# Qwiic_Shield_for_Arduino.net
KiCad netlist of a schematic drawn in EAGLE
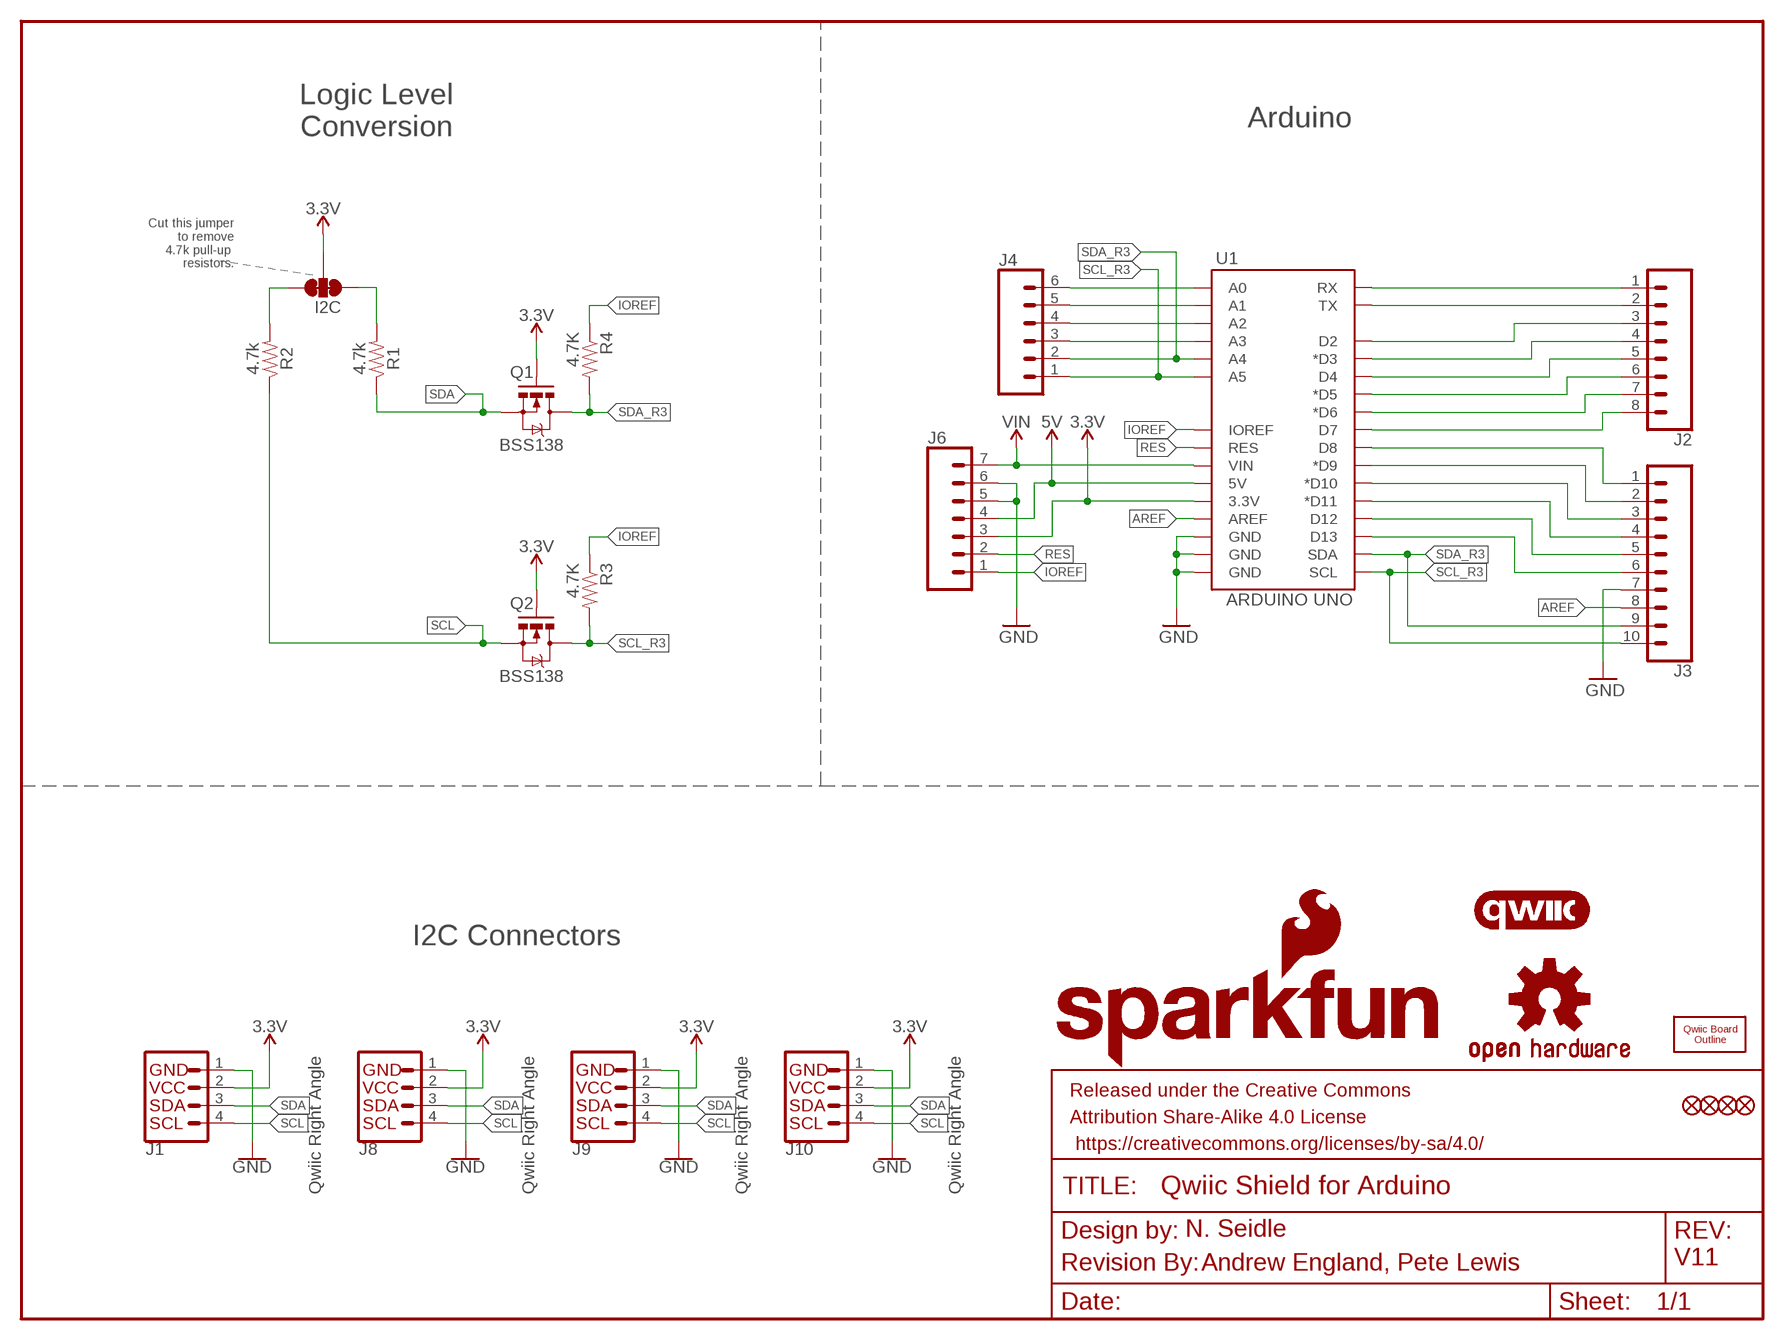
[diagram p0: schematic, sheet 1]

(export (version "E")
  (design (tool "Eeschema 10.0.6"))
  (components
    (comp (ref "FD1")
      (value "FIDUCIAL1X2")
      (footprint "eagle-import:FIDUCIAL-1X2")
      (libsource (lib "eagle-import") (part "FIDUCIAL1X2"))
    )
    (comp (ref "FD2")
      (value "FIDUCIAL1X2")
      (footprint "eagle-import:FIDUCIAL-1X2")
      (libsource (lib "eagle-import") (part "FIDUCIAL1X2"))
    )
    (comp (ref "FD3")
      (value "FIDUCIAL1X2")
      (footprint "eagle-import:FIDUCIAL-1X2")
      (libsource (lib "eagle-import") (part "FIDUCIAL1X2"))
    )
    (comp (ref "FD4")
      (value "FIDUCIAL1X2")
      (footprint "eagle-import:FIDUCIAL-1X2")
      (libsource (lib "eagle-import") (part "FIDUCIAL1X2"))
    )
    (comp (ref "FRAME1")
      (value "FRAME-LETTER")
      (footprint "eagle-import:CREATIVE_COMMONS")
      (libsource (lib "eagle-import") (part "FRAME-LETTER"))
    )
    (comp (ref "I2C")
      (value "JUMPER-SMT_3_2-NC_TRACE_SILK")
      (footprint "eagle-import:SMT-JUMPER_3_2-NC_TRACE_SILK")
      (libsource (lib "eagle-import") (part "JUMPER-SMT_3_2-NC_TRACE_SILK"))
    )
    (comp (ref "J1")
      (value "Qwiic Right Angle")
      (footprint "eagle-import:1X04_1MM_RA")
      (libsource (lib "eagle-import") (part "I2C_STANDARDQWIIC"))
    )
    (comp (ref "J2")
      (value "CONN_08NO_SILK_FEMALE_PTH")
      (footprint "eagle-import:1X08_NO_SILK")
      (libsource (lib "eagle-import") (part "CONN_08NO_SILK_FEMALE_PTH"))
    )
    (comp (ref "J3")
      (value "CONN_10NO_SILK_PTH_FEMALE")
      (footprint "eagle-import:1X10_NO_SILK")
      (libsource (lib "eagle-import") (part "CONN_10NO_SILK_PTH_FEMALE"))
    )
    (comp (ref "J4")
      (value "CONN_06NO_SILK_FEMALE_PTH")
      (footprint "eagle-import:1X06_NO_SILK")
      (libsource (lib "eagle-import") (part "CONN_06NO_SILK_FEMALE_PTH"))
    )
    (comp (ref "J6")
      (value "CONN_07NO_SILK")
      (footprint "eagle-import:1X07_NO_SILK")
      (libsource (lib "eagle-import") (part "CONN_07NO_SILK"))
    )
    (comp (ref "J8")
      (value "Qwiic Right Angle")
      (footprint "eagle-import:1X04_1MM_RA")
      (libsource (lib "eagle-import") (part "I2C_STANDARDQWIIC"))
    )
    (comp (ref "J9")
      (value "Qwiic Right Angle")
      (footprint "eagle-import:1X04_1MM_RA")
      (libsource (lib "eagle-import") (part "I2C_STANDARDQWIIC"))
    )
    (comp (ref "J10")
      (value "Qwiic Right Angle")
      (footprint "eagle-import:1X04_1MM_RA")
      (libsource (lib "eagle-import") (part "I2C_STANDARDQWIIC"))
    )
    (comp (ref "LOGO1")
      (value "OSHW-LOGOMINI")
      (footprint "eagle-import:OSHW-LOGO-MINI")
      (libsource (lib "eagle-import") (part "OSHW-LOGOMINI"))
    )
    (comp (ref "LOGO2")
      (value "REVISION")
      (footprint "eagle-import:REVISION")
      (libsource (lib "eagle-import") (part "REVISION"))
    )
    (comp (ref "LOGO3")
      (value "QWIIC_LOGO_6MM")
      (footprint "eagle-import:QWIIC_6MM")
      (libsource (lib "eagle-import") (part "QWIIC_LOGO_6MM"))
    )
    (comp (ref "Q1")
      (value "BSS138")
      (footprint "eagle-import:SOT23-3")
      (libsource (lib "eagle-import") (part "MOSFET-NCHANNELBSS138"))
    )
    (comp (ref "Q2")
      (value "BSS138")
      (footprint "eagle-import:SOT23-3")
      (libsource (lib "eagle-import") (part "MOSFET-NCHANNELBSS138"))
    )
    (comp (ref "R1")
      (value "4.7k")
      (footprint "eagle-import:0603")
      (libsource (lib "eagle-import") (part "4.7KOHM-0603-1/10W-1%"))
    )
    (comp (ref "R2")
      (value "4.7k")
      (footprint "eagle-import:0603")
      (libsource (lib "eagle-import") (part "4.7KOHM-0603-1/10W-1%"))
    )
    (comp (ref "R3")
      (value "4.7K")
      (footprint "eagle-import:0603-RES")
      (libsource (lib "eagle-import") (part "4.7KOHM-1/10W-1%(0603)"))
    )
    (comp (ref "R4")
      (value "4.7K")
      (footprint "eagle-import:0603-RES")
      (libsource (lib "eagle-import") (part "4.7KOHM-1/10W-1%(0603)"))
    )
    (comp (ref "U$2")
      (value "SFE_LOGO_NAME_FLAME.1_INCH")
      (footprint "eagle-import:SFE_LOGO_NAME_FLAME_.1")
      (libsource (lib "eagle-import") (part "SFE_LOGO_NAME_FLAME.1_INCH"))
    )
    (comp (ref "U$3")
      (value "QWIIC_BOARD_OUTLINEH")
      (footprint "eagle-import:QWIIC_BOARD_MOUNT_HOLES")
      (libsource (lib "eagle-import") (part "QWIIC_BOARD_OUTLINEH"))
    )
    (comp (ref "U1")
      (value "ARDUINO UNO")
      (footprint "eagle-import:UNO_R3_SHIELD_NOLABELS")
      (libsource (lib "eagle-import") (part "ARDUINO_R3_SHIELDNOLABELS"))
    )
  )
  (nets
    (net (code "1") (name "3.3V") (class "Default")
      (node (ref "I2C") (pin "2") (pinfunction "2_2") (pintype "passive"))
      (node (ref "J1") (pin "2") (pinfunction "2_2") (pintype "power_in"))
      (node (ref "J10") (pin "2") (pinfunction "2_2") (pintype "power_in"))
      (node (ref "J6") (pin "3") (pinfunction "3_3") (pintype "passive"))
      (node (ref "J8") (pin "2") (pinfunction "2_2") (pintype "power_in"))
      (node (ref "J9") (pin "2") (pinfunction "2_2") (pintype "power_in"))
      (node (ref "Q1") (pin "1") (pinfunction "G_1") (pintype "passive"))
      (node (ref "Q2") (pin "1") (pinfunction "G_1") (pintype "passive"))
      (node (ref "U1") (pin "3.3V") (pinfunction "3.3V_3.3V") (pintype "bidirectional"))
    )
    (net (code "2") (name "5V") (class "Default")
      (node (ref "J6") (pin "4") (pinfunction "4_4") (pintype "passive"))
      (node (ref "U1") (pin "5V") (pinfunction "5V_5V") (pintype "bidirectional"))
    )
    (net (code "3") (name "AREF") (class "Default")
      (node (ref "J3") (pin "8") (pinfunction "8_8") (pintype "passive"))
      (node (ref "U1") (pin "AREF") (pinfunction "AREF_AREF") (pintype "bidirectional"))
    )
    (net (code "4") (name "GND") (class "Default")
      (node (ref "J1") (pin "1") (pinfunction "1_1") (pintype "power_in"))
      (node (ref "J10") (pin "1") (pinfunction "1_1") (pintype "power_in"))
      (node (ref "J3") (pin "7") (pinfunction "7_7") (pintype "passive"))
      (node (ref "J6") (pin "5") (pinfunction "5_5") (pintype "passive"))
      (node (ref "J6") (pin "6") (pinfunction "6_6") (pintype "passive"))
      (node (ref "J8") (pin "1") (pinfunction "1_1") (pintype "power_in"))
      (node (ref "J9") (pin "1") (pinfunction "1_1") (pintype "power_in"))
      (node (ref "U1") (pin "GND@0") (pinfunction "GND_GND@0") (pintype "bidirectional"))
      (node (ref "U1") (pin "GND@1") (pinfunction "GND_GND@1") (pintype "bidirectional"))
      (node (ref "U1") (pin "GND@2") (pinfunction "GND_GND@2") (pintype "bidirectional"))
    )
    (net (code "5") (name "IOREF") (class "Default")
      (node (ref "J6") (pin "1") (pinfunction "1_1") (pintype "passive"))
      (node (ref "R3") (pin "1") (pinfunction "1_1") (pintype "passive"))
      (node (ref "R4") (pin "1") (pinfunction "1_1") (pintype "passive"))
      (node (ref "U1") (pin "IOREF") (pinfunction "IOREF_IOREF") (pintype "bidirectional"))
    )
    (net (code "6") (name "Net-(I2C-Pad1)") (class "Default")
      (node (ref "I2C") (pin "1") (pinfunction "1_1") (pintype "passive"))
      (node (ref "R2") (pin "2") (pinfunction "2_2") (pintype "passive"))
    )
    (net (code "7") (name "Net-(I2C-Pad3)") (class "Default")
      (node (ref "I2C") (pin "3") (pinfunction "3_3") (pintype "passive"))
      (node (ref "R1") (pin "2") (pinfunction "2_2") (pintype "passive"))
    )
    (net (code "8") (name "Net-(J2-Pad1)") (class "Default")
      (node (ref "J2") (pin "1") (pinfunction "1_1") (pintype "passive"))
      (node (ref "U1") (pin "RX") (pinfunction "RX_RX") (pintype "bidirectional"))
    )
    (net (code "9") (name "Net-(J2-Pad2)") (class "Default")
      (node (ref "J2") (pin "2") (pinfunction "2_2") (pintype "passive"))
      (node (ref "U1") (pin "TX") (pinfunction "TX_TX") (pintype "bidirectional"))
    )
    (net (code "10") (name "Net-(J2-Pad3)") (class "Default")
      (node (ref "J2") (pin "3") (pinfunction "3_3") (pintype "passive"))
      (node (ref "U1") (pin "D2") (pinfunction "D2_D2") (pintype "bidirectional"))
    )
    (net (code "11") (name "Net-(J2-Pad5)") (class "Default")
      (node (ref "J2") (pin "5") (pinfunction "5_5") (pintype "passive"))
      (node (ref "U1") (pin "D4") (pinfunction "D4_D4") (pintype "bidirectional"))
    )
    (net (code "12") (name "Net-(J2-Pad8)") (class "Default")
      (node (ref "J2") (pin "8") (pinfunction "8_8") (pintype "passive"))
      (node (ref "U1") (pin "D7") (pinfunction "D7_D7") (pintype "bidirectional"))
    )
    (net (code "13") (name "Net-(J3-Pad1)") (class "Default")
      (node (ref "J3") (pin "1") (pinfunction "1_1") (pintype "passive"))
      (node (ref "U1") (pin "D8") (pinfunction "D8_D8") (pintype "bidirectional"))
    )
    (net (code "14") (name "Net-(J3-Pad5)") (class "Default")
      (node (ref "J3") (pin "5") (pinfunction "5_5") (pintype "passive"))
      (node (ref "U1") (pin "D12") (pinfunction "D12_D12") (pintype "bidirectional"))
    )
    (net (code "15") (name "Net-(J3-Pad6)") (class "Default")
      (node (ref "J3") (pin "6") (pinfunction "6_6") (pintype "passive"))
      (node (ref "U1") (pin "D13") (pinfunction "D13_D13") (pintype "bidirectional"))
    )
    (net (code "16") (name "Net-(J4-Pad3)") (class "Default")
      (node (ref "J4") (pin "3") (pinfunction "3_3") (pintype "passive"))
      (node (ref "U1") (pin "A3") (pinfunction "A3_A3") (pintype "bidirectional"))
    )
    (net (code "17") (name "Net-(J4-Pad4)") (class "Default")
      (node (ref "J4") (pin "4") (pinfunction "4_4") (pintype "passive"))
      (node (ref "U1") (pin "A2") (pinfunction "A2_A2") (pintype "bidirectional"))
    )
    (net (code "18") (name "Net-(J4-Pad5)") (class "Default")
      (node (ref "J4") (pin "5") (pinfunction "5_5") (pintype "passive"))
      (node (ref "U1") (pin "A1") (pinfunction "A1_A1") (pintype "bidirectional"))
    )
    (net (code "19") (name "Net-(J4-Pad6)") (class "Default")
      (node (ref "J4") (pin "6") (pinfunction "6_6") (pintype "passive"))
      (node (ref "U1") (pin "A0") (pinfunction "A0_A0") (pintype "bidirectional"))
    )
    (net (code "20") (name "Net-(U1-*D3)") (class "Default")
      (node (ref "J2") (pin "4") (pinfunction "4_4") (pintype "passive"))
      (node (ref "U1") (pin "D3") (pinfunction "*D3_D3") (pintype "bidirectional"))
    )
    (net (code "21") (name "Net-(U1-*D5)") (class "Default")
      (node (ref "J2") (pin "6") (pinfunction "6_6") (pintype "passive"))
      (node (ref "U1") (pin "D5") (pinfunction "*D5_D5") (pintype "bidirectional"))
    )
    (net (code "22") (name "Net-(U1-*D6)") (class "Default")
      (node (ref "J2") (pin "7") (pinfunction "7_7") (pintype "passive"))
      (node (ref "U1") (pin "D6") (pinfunction "*D6_D6") (pintype "bidirectional"))
    )
    (net (code "23") (name "Net-(U1-*D9)") (class "Default")
      (node (ref "J3") (pin "2") (pinfunction "2_2") (pintype "passive"))
      (node (ref "U1") (pin "D9") (pinfunction "*D9_D9") (pintype "bidirectional"))
    )
    (net (code "24") (name "Net-(U1-*D10)") (class "Default")
      (node (ref "J3") (pin "3") (pinfunction "3_3") (pintype "passive"))
      (node (ref "U1") (pin "D10") (pinfunction "*D10_D10") (pintype "bidirectional"))
    )
    (net (code "25") (name "Net-(U1-*D11)") (class "Default")
      (node (ref "J3") (pin "4") (pinfunction "4_4") (pintype "passive"))
      (node (ref "U1") (pin "D11") (pinfunction "*D11_D11") (pintype "bidirectional"))
    )
    (net (code "26") (name "RES") (class "Default")
      (node (ref "J6") (pin "2") (pinfunction "2_2") (pintype "passive"))
      (node (ref "U1") (pin "RES") (pinfunction "RES_RES") (pintype "bidirectional"))
    )
    (net (code "27") (name "SCL") (class "Default")
      (node (ref "J1") (pin "4") (pinfunction "4_4") (pintype "passive"))
      (node (ref "J10") (pin "4") (pinfunction "4_4") (pintype "passive"))
      (node (ref "J8") (pin "4") (pinfunction "4_4") (pintype "passive"))
      (node (ref "J9") (pin "4") (pinfunction "4_4") (pintype "passive"))
      (node (ref "Q2") (pin "2") (pinfunction "S_2") (pintype "passive"))
      (node (ref "R2") (pin "1") (pinfunction "1_1") (pintype "passive"))
    )
    (net (code "28") (name "SCL_R3") (class "Default")
      (node (ref "J3") (pin "10") (pinfunction "10_10") (pintype "passive"))
      (node (ref "J4") (pin "1") (pinfunction "1_1") (pintype "passive"))
      (node (ref "Q2") (pin "3") (pinfunction "D_3") (pintype "passive"))
      (node (ref "R3") (pin "2") (pinfunction "2_2") (pintype "passive"))
      (node (ref "U1") (pin "A5") (pinfunction "A5_A5") (pintype "bidirectional"))
      (node (ref "U1") (pin "SCL") (pinfunction "SCL_SCL") (pintype "bidirectional"))
    )
    (net (code "29") (name "SDA") (class "Default")
      (node (ref "J1") (pin "3") (pinfunction "3_3") (pintype "passive"))
      (node (ref "J10") (pin "3") (pinfunction "3_3") (pintype "passive"))
      (node (ref "J8") (pin "3") (pinfunction "3_3") (pintype "passive"))
      (node (ref "J9") (pin "3") (pinfunction "3_3") (pintype "passive"))
      (node (ref "Q1") (pin "2") (pinfunction "S_2") (pintype "passive"))
      (node (ref "R1") (pin "1") (pinfunction "1_1") (pintype "passive"))
    )
    (net (code "30") (name "SDA_R3") (class "Default")
      (node (ref "J3") (pin "9") (pinfunction "9_9") (pintype "passive"))
      (node (ref "J4") (pin "2") (pinfunction "2_2") (pintype "passive"))
      (node (ref "Q1") (pin "3") (pinfunction "D_3") (pintype "passive"))
      (node (ref "R4") (pin "2") (pinfunction "2_2") (pintype "passive"))
      (node (ref "U1") (pin "A4") (pinfunction "A4_A4") (pintype "bidirectional"))
      (node (ref "U1") (pin "SDA") (pinfunction "SDA_SDA") (pintype "bidirectional"))
    )
    (net (code "31") (name "VIN") (class "Default")
      (node (ref "J6") (pin "7") (pinfunction "7_7") (pintype "passive"))
      (node (ref "U1") (pin "VIN") (pinfunction "VIN_VIN") (pintype "bidirectional"))
    )
  )
)
